# W25X40_BREAKOUT.net
KiCad netlist of a schematic drawn in EAGLE
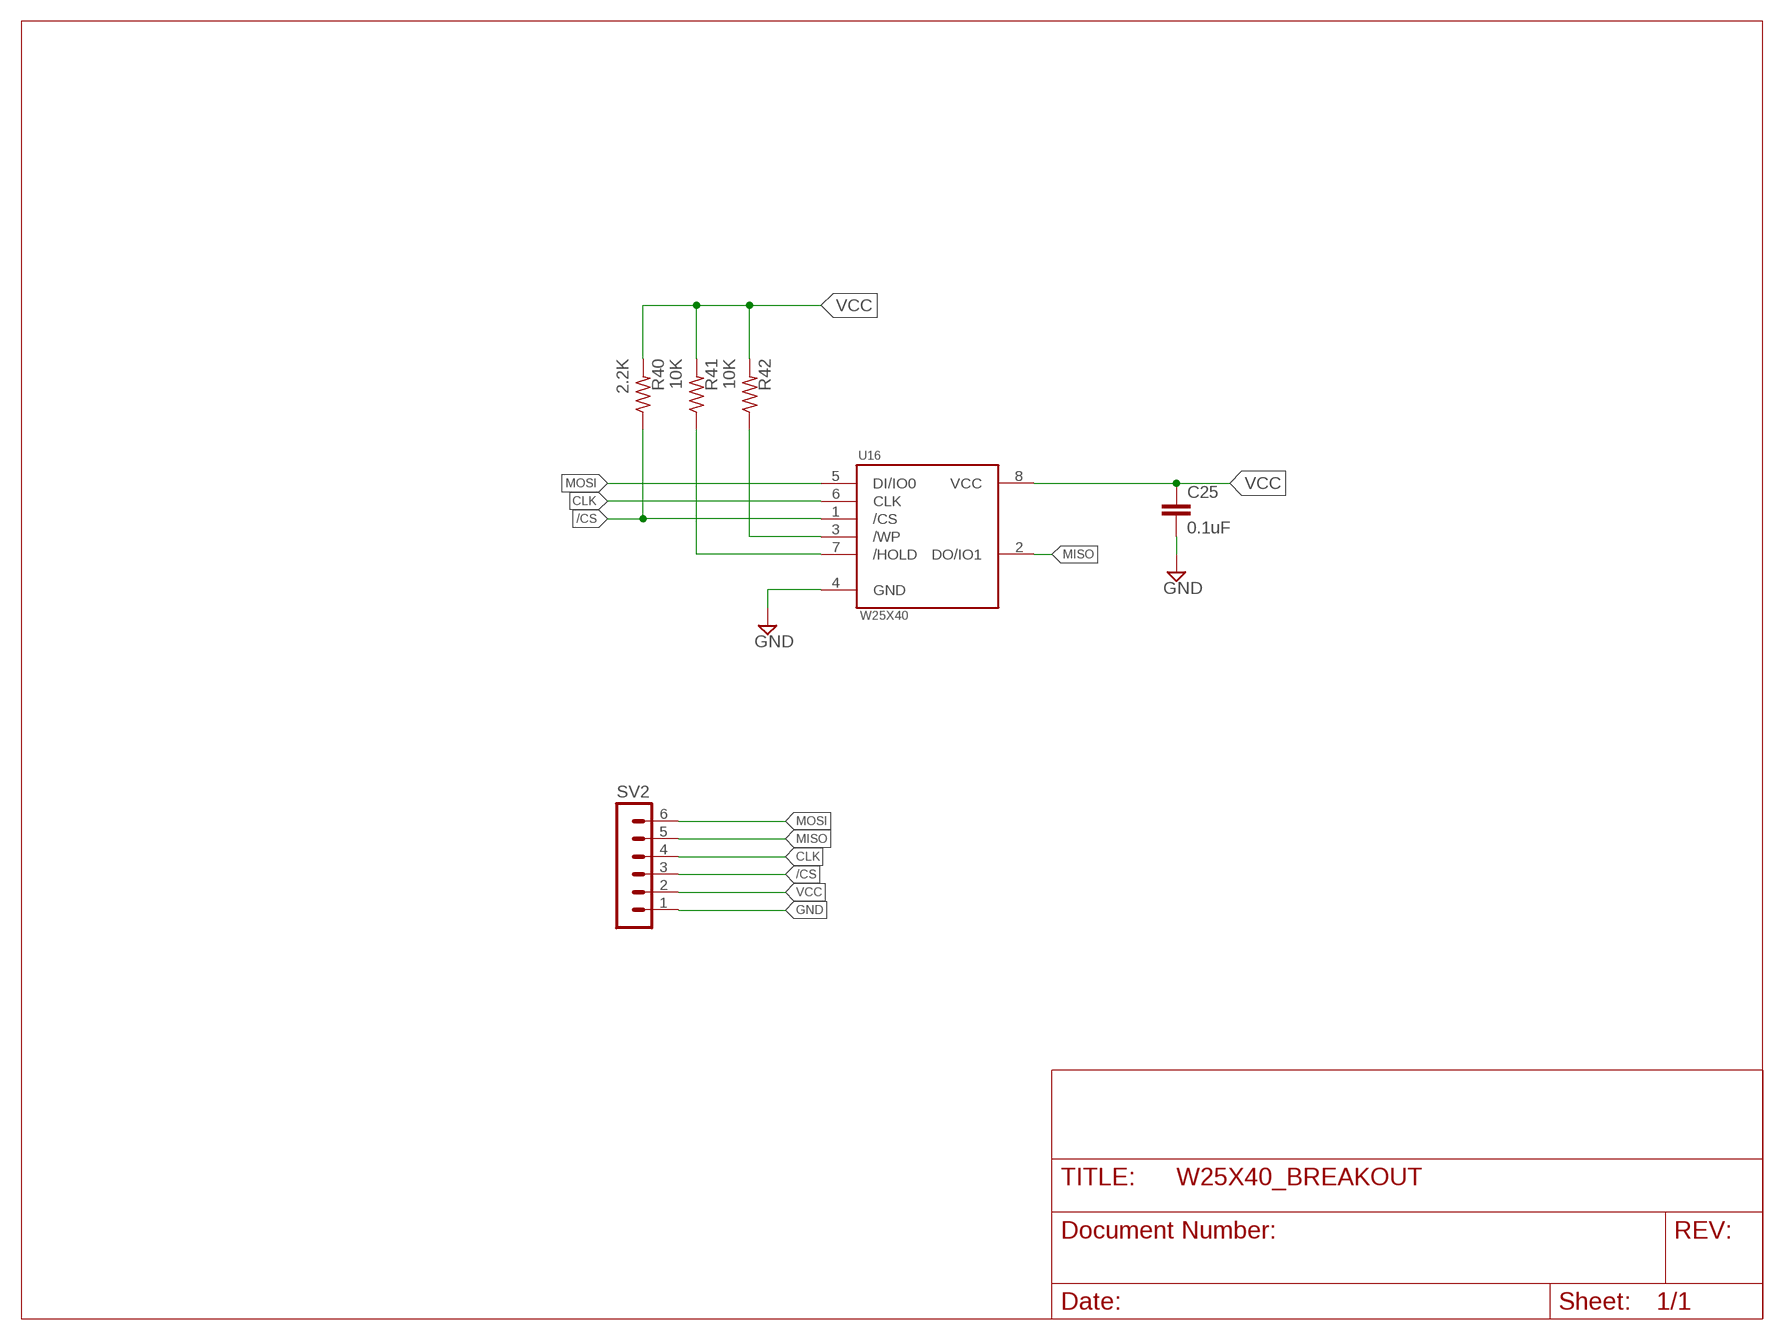
[diagram p0: schematic, sheet 1]

(export (version "E")
  (design (tool "Eeschema 10.0.6"))
  (components
    (comp (ref "C25")
      (value "0.1uF")
      (footprint "eagle-import:C025-030X050")
      (libsource (lib "eagle-import") (part "C-EU025-030X050"))
    )
    (comp (ref "R40")
      (value "2.2K")
      (footprint "eagle-import:0204_7")
      (libsource (lib "eagle-import") (part "R-EU_0204/7"))
    )
    (comp (ref "R41")
      (value "10K")
      (footprint "eagle-import:0204_7")
      (libsource (lib "eagle-import") (part "R-EU_0204/7"))
    )
    (comp (ref "R42")
      (value "10K")
      (footprint "eagle-import:0204_7")
      (libsource (lib "eagle-import") (part "R-EU_0204/7"))
    )
    (comp (ref "SV2")
      (value "MA06-1")
      (footprint "eagle-import:MA06-1")
      (libsource (lib "eagle-import") (part "MA06-1"))
    )
    (comp (ref "U16")
      (value "W25X40CLUXIG")
      (footprint "eagle-import:SOIC8")
      (libsource (lib "eagle-import") (part "W25X40CLUXIG"))
    )
  )
  (nets
    (net (code "1") (name "CLK") (class "Default")
      (node (ref "SV2") (pin "4") (pinfunction "4_4") (pintype "passive"))
      (node (ref "U16") (pin "6") (pinfunction "CLK_6") (pintype "bidirectional"))
    )
    (net (code "2") (name "GND") (class "Default")
      (node (ref "C25") (pin "2") (pinfunction "2_2") (pintype "passive"))
      (node (ref "SV2") (pin "1") (pinfunction "1_1") (pintype "passive"))
      (node (ref "U16") (pin "4") (pinfunction "GND_4") (pintype "bidirectional"))
    )
    (net (code "3") (name "MISO") (class "Default")
      (node (ref "SV2") (pin "5") (pinfunction "5_5") (pintype "passive"))
      (node (ref "U16") (pin "2") (pinfunction "DO/IO1_2") (pintype "bidirectional"))
    )
    (net (code "4") (name "MOSI") (class "Default")
      (node (ref "SV2") (pin "6") (pinfunction "6_6") (pintype "passive"))
      (node (ref "U16") (pin "5") (pinfunction "DI/IO0_5") (pintype "bidirectional"))
    )
    (net (code "5") (name "Net-(U16-{slash}HOLD)") (class "Default")
      (node (ref "R41") (pin "1") (pinfunction "1_1") (pintype "passive"))
      (node (ref "U16") (pin "7") (pinfunction "/HOLD_7") (pintype "bidirectional"))
    )
    (net (code "6") (name "Net-(U16-{slash}WP)") (class "Default")
      (node (ref "R42") (pin "1") (pinfunction "1_1") (pintype "passive"))
      (node (ref "U16") (pin "3") (pinfunction "/WP_3") (pintype "bidirectional"))
    )
    (net (code "7") (name "VCC") (class "Default")
      (node (ref "C25") (pin "1") (pinfunction "1_1") (pintype "passive"))
      (node (ref "R40") (pin "2") (pinfunction "2_2") (pintype "passive"))
      (node (ref "R41") (pin "2") (pinfunction "2_2") (pintype "passive"))
      (node (ref "R42") (pin "2") (pinfunction "2_2") (pintype "passive"))
      (node (ref "SV2") (pin "2") (pinfunction "2_2") (pintype "passive"))
      (node (ref "U16") (pin "8") (pinfunction "VCC_8") (pintype "bidirectional"))
    )
    (net (code "8") (name "{slash}CS") (class "Default")
      (node (ref "R40") (pin "1") (pinfunction "1_1") (pintype "passive"))
      (node (ref "SV2") (pin "3") (pinfunction "3_3") (pintype "passive"))
      (node (ref "U16") (pin "1") (pinfunction "/CS_1") (pintype "bidirectional"))
    )
  )
)
